# Rover_PI_hat.net
KiCad netlist of a schematic drawn in Altium Designer
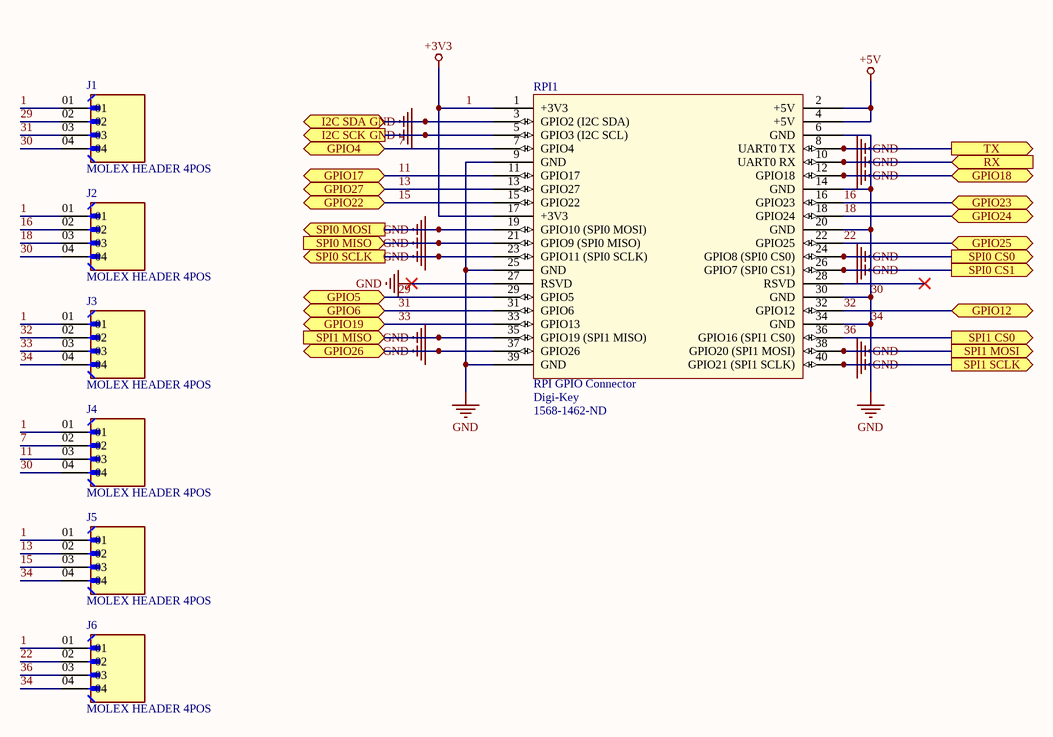
[diagram p0: Rover_PI_hat.SchDoc]

(export (version "E")
  (design (tool "Eeschema 10.0.6"))
  (components
    (comp (ref "J1")
      (value "MOLEX HEADER 4POS")
      (footprint "MOLEX_35362-0450")
      (description "Connector Header Through Hole 4 position 0.079 (2.00mm)")
      (fields (field (name "MP") "35362-0450") (field (name "MF") "Molex"))
      (libsource (lib "35362-0450") (part "35362-0450"))
    )
    (comp (ref "J2")
      (value "MOLEX HEADER 4POS")
      (footprint "MOLEX_35362-0450")
      (description "Connector Header Through Hole 4 position 0.079 (2.00mm)")
      (fields (field (name "MP") "35362-0450") (field (name "MF") "Molex"))
      (libsource (lib "35362-0450") (part "35362-0450"))
    )
    (comp (ref "J3")
      (value "MOLEX HEADER 4POS")
      (footprint "MOLEX_35362-0450")
      (description "Connector Header Through Hole 4 position 0.079 (2.00mm)")
      (fields (field (name "MP") "35362-0450") (field (name "MF") "Molex"))
      (libsource (lib "35362-0450") (part "35362-0450"))
    )
    (comp (ref "J4")
      (value "MOLEX HEADER 4POS")
      (footprint "MOLEX_35362-0450")
      (description "Connector Header Through Hole 4 position 0.079 (2.00mm)")
      (fields (field (name "MP") "35362-0450") (field (name "MF") "Molex"))
      (libsource (lib "35362-0450") (part "35362-0450"))
    )
    (comp (ref "J5")
      (value "MOLEX HEADER 4POS")
      (footprint "MOLEX_35362-0450")
      (description "Connector Header Through Hole 4 position 0.079 (2.00mm)")
      (fields (field (name "MP") "35362-0450") (field (name "MF") "Molex"))
      (libsource (lib "35362-0450") (part "35362-0450"))
    )
    (comp (ref "J6")
      (value "MOLEX HEADER 4POS")
      (footprint "MOLEX_35362-0450")
      (description "Connector Header Through Hole 4 position 0.079 (2.00mm)")
      (fields (field (name "MP") "35362-0450") (field (name "MF") "Molex"))
      (libsource (lib "35362-0450") (part "35362-0450"))
    )
    (comp (ref "RPI1")
      (value "RPI GPIO Connector")
      (footprint "rpi")
      (description "GPIO Header for Raspberry Pi A+/B+/Pi 2/Pi 3 - 2x20")
      (fields
        (field (name "MANUFACTURER") "SparkFun Electronics")
        (field (name "MANUFACTURER PART NUMBER") "PRT-14017")
        (field (name "SUPPLIER 1") "Digi-Key")
        (field (name "SUPPLIER PART NUMBER 1") "1568-1462-ND")
      )
      (libsource (lib "rpi") (part "rpi connector"))
    )
  )
  (nets
    (net (code "1") (name "+3V3") (class "Default")
      (node (ref "J1") (pin "01") (pinfunction "01_01") (pintype "passive"))
      (node (ref "J2") (pin "01") (pinfunction "01_01") (pintype "passive"))
      (node (ref "J3") (pin "01") (pinfunction "01_01") (pintype "passive"))
      (node (ref "J4") (pin "01") (pinfunction "01_01") (pintype "passive"))
      (node (ref "J5") (pin "01") (pinfunction "01_01") (pintype "passive"))
      (node (ref "J6") (pin "01") (pinfunction "01_01") (pintype "passive"))
      (node (ref "RPI1") (pin "1") (pinfunction "+3V3_1") (pintype "power_in"))
      (node (ref "RPI1") (pin "17") (pinfunction "+3V3_17") (pintype "power_in"))
    )
    (net (code "2") (name "+5V") (class "Default")
      (node (ref "RPI1") (pin "2") (pinfunction "+5V_2") (pintype "power_in"))
      (node (ref "RPI1") (pin "4") (pinfunction "+5V_4") (pintype "power_in"))
    )
    (net (code "3") (name "/7") (class "Default")
      (node (ref "J4") (pin "02") (pinfunction "02_02") (pintype "passive"))
      (node (ref "RPI1") (pin "7") (pinfunction "GPIO4_7") (pintype "bidirectional"))
    )
    (net (code "4") (name "/11") (class "Default")
      (node (ref "J4") (pin "03") (pinfunction "03_03") (pintype "passive"))
      (node (ref "RPI1") (pin "11") (pinfunction "GPIO17_11") (pintype "bidirectional"))
    )
    (net (code "5") (name "/13") (class "Default")
      (node (ref "J5") (pin "02") (pinfunction "02_02") (pintype "passive"))
      (node (ref "RPI1") (pin "13") (pinfunction "GPIO27_13") (pintype "bidirectional"))
    )
    (net (code "6") (name "/15") (class "Default")
      (node (ref "J5") (pin "03") (pinfunction "03_03") (pintype "passive"))
      (node (ref "RPI1") (pin "15") (pinfunction "GPIO22_15") (pintype "bidirectional"))
    )
    (net (code "7") (name "/16") (class "Default")
      (node (ref "J2") (pin "02") (pinfunction "02_02") (pintype "passive"))
      (node (ref "RPI1") (pin "16") (pinfunction "GPIO23_16") (pintype "bidirectional"))
    )
    (net (code "8") (name "/18") (class "Default")
      (node (ref "J2") (pin "03") (pinfunction "03_03") (pintype "passive"))
      (node (ref "RPI1") (pin "18") (pinfunction "GPIO24_18") (pintype "bidirectional"))
    )
    (net (code "9") (name "/22") (class "Default")
      (node (ref "J6") (pin "02") (pinfunction "02_02") (pintype "passive"))
      (node (ref "RPI1") (pin "22") (pinfunction "GPIO25_22") (pintype "bidirectional"))
    )
    (net (code "10") (name "/29") (class "Default")
      (node (ref "J1") (pin "02") (pinfunction "02_02") (pintype "passive"))
      (node (ref "RPI1") (pin "29") (pinfunction "GPIO5_29") (pintype "bidirectional"))
    )
    (net (code "11") (name "/31") (class "Default")
      (node (ref "J1") (pin "03") (pinfunction "03_03") (pintype "passive"))
      (node (ref "RPI1") (pin "31") (pinfunction "GPIO6_31") (pintype "bidirectional"))
    )
    (net (code "12") (name "/32") (class "Default")
      (node (ref "J3") (pin "02") (pinfunction "02_02") (pintype "passive"))
      (node (ref "RPI1") (pin "32") (pinfunction "GPIO12_32") (pintype "bidirectional"))
    )
    (net (code "13") (name "/33") (class "Default")
      (node (ref "J3") (pin "03") (pinfunction "03_03") (pintype "passive"))
      (node (ref "RPI1") (pin "33") (pinfunction "GPIO13_33") (pintype "bidirectional"))
    )
    (net (code "14") (name "/36") (class "Default")
      (node (ref "J6") (pin "03") (pinfunction "03_03") (pintype "passive"))
      (node (ref "RPI1") (pin "36") (pinfunction "GPIO16_(SPI1_CS0)_36") (pintype "bidirectional"))
    )
    (net (code "15") (name "GND") (class "Default")
      (node (ref "J1") (pin "04") (pinfunction "04_04") (pintype "passive"))
      (node (ref "J2") (pin "04") (pinfunction "04_04") (pintype "passive"))
      (node (ref "J3") (pin "04") (pinfunction "04_04") (pintype "passive"))
      (node (ref "J4") (pin "04") (pinfunction "04_04") (pintype "passive"))
      (node (ref "J5") (pin "04") (pinfunction "04_04") (pintype "passive"))
      (node (ref "J6") (pin "04") (pinfunction "04_04") (pintype "passive"))
      (node (ref "RPI1") (pin "10") (pinfunction "UART0_RX_10") (pintype "bidirectional"))
      (node (ref "RPI1") (pin "12") (pinfunction "GPIO18_12") (pintype "bidirectional"))
      (node (ref "RPI1") (pin "14") (pinfunction "GND_14") (pintype "power_in"))
      (node (ref "RPI1") (pin "19") (pinfunction "GPIO10_(SPI0_MOSI)_19") (pintype "bidirectional"))
      (node (ref "RPI1") (pin "20") (pinfunction "GND_20") (pintype "power_in"))
      (node (ref "RPI1") (pin "21") (pinfunction "GPIO9_(SPI0_MISO)_21") (pintype "bidirectional"))
      (node (ref "RPI1") (pin "23") (pinfunction "GPIO11_(SPI0_SCLK)_23") (pintype "bidirectional"))
      (node (ref "RPI1") (pin "24") (pinfunction "GPIO8_(SPI0_CS0)_24") (pintype "bidirectional"))
      (node (ref "RPI1") (pin "25") (pinfunction "GND_25") (pintype "power_in"))
      (node (ref "RPI1") (pin "26") (pinfunction "GPIO7_(SPI0_CS1)_26") (pintype "bidirectional"))
      (node (ref "RPI1") (pin "27") (pinfunction "RSVD_27") (pintype "passive"))
      (node (ref "RPI1") (pin "3") (pinfunction "GPIO2_(I2C_SDA)_3") (pintype "bidirectional"))
      (node (ref "RPI1") (pin "30") (pinfunction "GND_30") (pintype "power_in"))
      (node (ref "RPI1") (pin "34") (pinfunction "GND_34") (pintype "passive"))
      (node (ref "RPI1") (pin "35") (pinfunction "GPIO19_(SPI1_MISO)_35") (pintype "bidirectional"))
      (node (ref "RPI1") (pin "37") (pinfunction "GPIO26_37") (pintype "bidirectional"))
      (node (ref "RPI1") (pin "38") (pinfunction "GPIO20_(SPI1_MOSI)_38") (pintype "bidirectional"))
      (node (ref "RPI1") (pin "39") (pinfunction "GND_39") (pintype "power_in"))
      (node (ref "RPI1") (pin "40") (pinfunction "GPIO21_(SPI1_SCLK)_40") (pintype "bidirectional"))
      (node (ref "RPI1") (pin "5") (pinfunction "GPIO3_(I2C_SCL)_5") (pintype "bidirectional"))
      (node (ref "RPI1") (pin "6") (pinfunction "GND_6") (pintype "power_in"))
      (node (ref "RPI1") (pin "8") (pinfunction "UART0_TX_8") (pintype "bidirectional"))
      (node (ref "RPI1") (pin "9") (pinfunction "GND_9") (pintype "power_in"))
    )
    (net (code "16") (name "unconnected-(RPI1-RSVD-Pad28)") (class "Default")
      (node (ref "RPI1") (pin "28") (pinfunction "RSVD_28") (pintype "passive+no_connect"))
    )
  )
)
